# Binky_LED.net
KiCad netlist of a schematic drawn in EAGLE
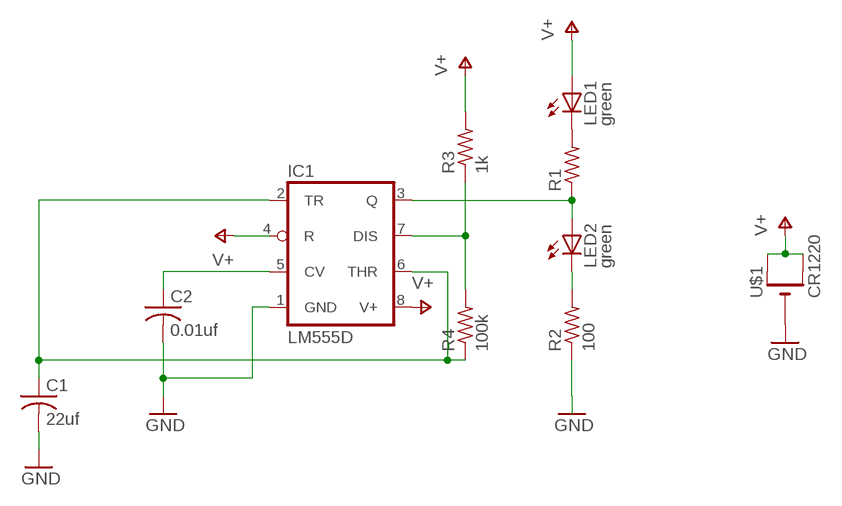
[diagram p0: schematic, sheet 1]

(export (version "E")
  (design (tool "Eeschema 10.0.6"))
  (components
    (comp (ref "C1")
      (value "22uf")
      (footprint "eagle-import:C0805")
      (libsource (lib "eagle-import") (part "C-USC0805"))
    )
    (comp (ref "C2")
      (value "0.01uf")
      (footprint "eagle-import:C0805")
      (libsource (lib "eagle-import") (part "C-USC0805"))
    )
    (comp (ref "IC1")
      (value "LM555D")
      (footprint "eagle-import:SO08")
      (libsource (lib "eagle-import") (part "555DLM"))
    )
    (comp (ref "LED1")
      (value "green")
      (footprint "eagle-import:CHIPLED_0805")
      (libsource (lib "eagle-import") (part "LEDCHIPLED_0805"))
    )
    (comp (ref "LED2")
      (value "green")
      (footprint "eagle-import:CHIPLED_0805")
      (libsource (lib "eagle-import") (part "LEDCHIPLED_0805"))
    )
    (comp (ref "R1")
      (value "R-US_R0805")
      (footprint "eagle-import:R0805")
      (libsource (lib "eagle-import") (part "R-US_R0805"))
    )
    (comp (ref "R2")
      (value "100")
      (footprint "eagle-import:R0805")
      (libsource (lib "eagle-import") (part "R-US_R0805"))
    )
    (comp (ref "R3")
      (value "1k")
      (footprint "eagle-import:R0805")
      (libsource (lib "eagle-import") (part "R-US_R0805"))
    )
    (comp (ref "R4")
      (value "100k")
      (footprint "eagle-import:R0805")
      (libsource (lib "eagle-import") (part "R-US_R0805"))
    )
    (comp (ref "U$1")
      (value "CR1220")
      (footprint "eagle-import:CR1220-SMD")
      (libsource (lib "eagle-import") (part "CR1220SMT"))
    )
  )
  (nets
    (net (code "1") (name "GND") (class "Default")
      (node (ref "C1") (pin "2") (pinfunction "2_2") (pintype "passive"))
      (node (ref "C2") (pin "2") (pinfunction "2_2") (pintype "passive"))
      (node (ref "IC1") (pin "1") (pinfunction "GND_1") (pintype "power_in"))
      (node (ref "R2") (pin "1") (pinfunction "1_1") (pintype "passive"))
      (node (ref "U$1") (pin "-") (pinfunction "-_-") (pintype "passive"))
    )
    (net (code "2") (name "Net-(IC1-CV)") (class "Default")
      (node (ref "C2") (pin "1") (pinfunction "1_1") (pintype "passive"))
      (node (ref "IC1") (pin "5") (pinfunction "CV_5") (pintype "input"))
    )
    (net (code "3") (name "Net-(IC1-DIS)") (class "Default")
      (node (ref "IC1") (pin "7") (pinfunction "DIS_7") (pintype "input"))
      (node (ref "R3") (pin "1") (pinfunction "1_1") (pintype "passive"))
      (node (ref "R4") (pin "2") (pinfunction "2_2") (pintype "passive"))
    )
    (net (code "4") (name "Net-(IC1-Q)") (class "Default")
      (node (ref "IC1") (pin "3") (pinfunction "Q_3") (pintype "output"))
      (node (ref "LED2") (pin "A") (pinfunction "A_A") (pintype "passive"))
      (node (ref "R1") (pin "1") (pinfunction "1_1") (pintype "passive"))
    )
    (net (code "5") (name "Net-(IC1-THR)") (class "Default")
      (node (ref "C1") (pin "1") (pinfunction "1_1") (pintype "passive"))
      (node (ref "IC1") (pin "2") (pinfunction "TR_2") (pintype "input"))
      (node (ref "IC1") (pin "6") (pinfunction "THR_6") (pintype "input"))
      (node (ref "R4") (pin "1") (pinfunction "1_1") (pintype "passive"))
    )
    (net (code "6") (name "Net-(LED1-PadC)") (class "Default")
      (node (ref "LED1") (pin "C") (pinfunction "C_C") (pintype "passive"))
      (node (ref "R1") (pin "2") (pinfunction "2_2") (pintype "passive"))
    )
    (net (code "7") (name "Net-(LED2-PadC)") (class "Default")
      (node (ref "LED2") (pin "C") (pinfunction "C_C") (pintype "passive"))
      (node (ref "R2") (pin "2") (pinfunction "2_2") (pintype "passive"))
    )
    (net (code "8") (name "V+") (class "Default")
      (node (ref "IC1") (pin "4") (pinfunction "R_4") (pintype "input"))
      (node (ref "IC1") (pin "8") (pinfunction "V+_8") (pintype "power_in"))
      (node (ref "LED1") (pin "A") (pinfunction "A_A") (pintype "passive"))
      (node (ref "R3") (pin "2") (pinfunction "2_2") (pintype "passive"))
      (node (ref "U$1") (pin "+$1") (pinfunction "+_+$1") (pintype "passive"))
      (node (ref "U$1") (pin "+$2") (pinfunction "+1_+$2") (pintype "passive"))
    )
  )
)
